# OpenPack_BATMOD_V2p0_USBA.net
KiCad netlist of a schematic drawn in Altium Designer
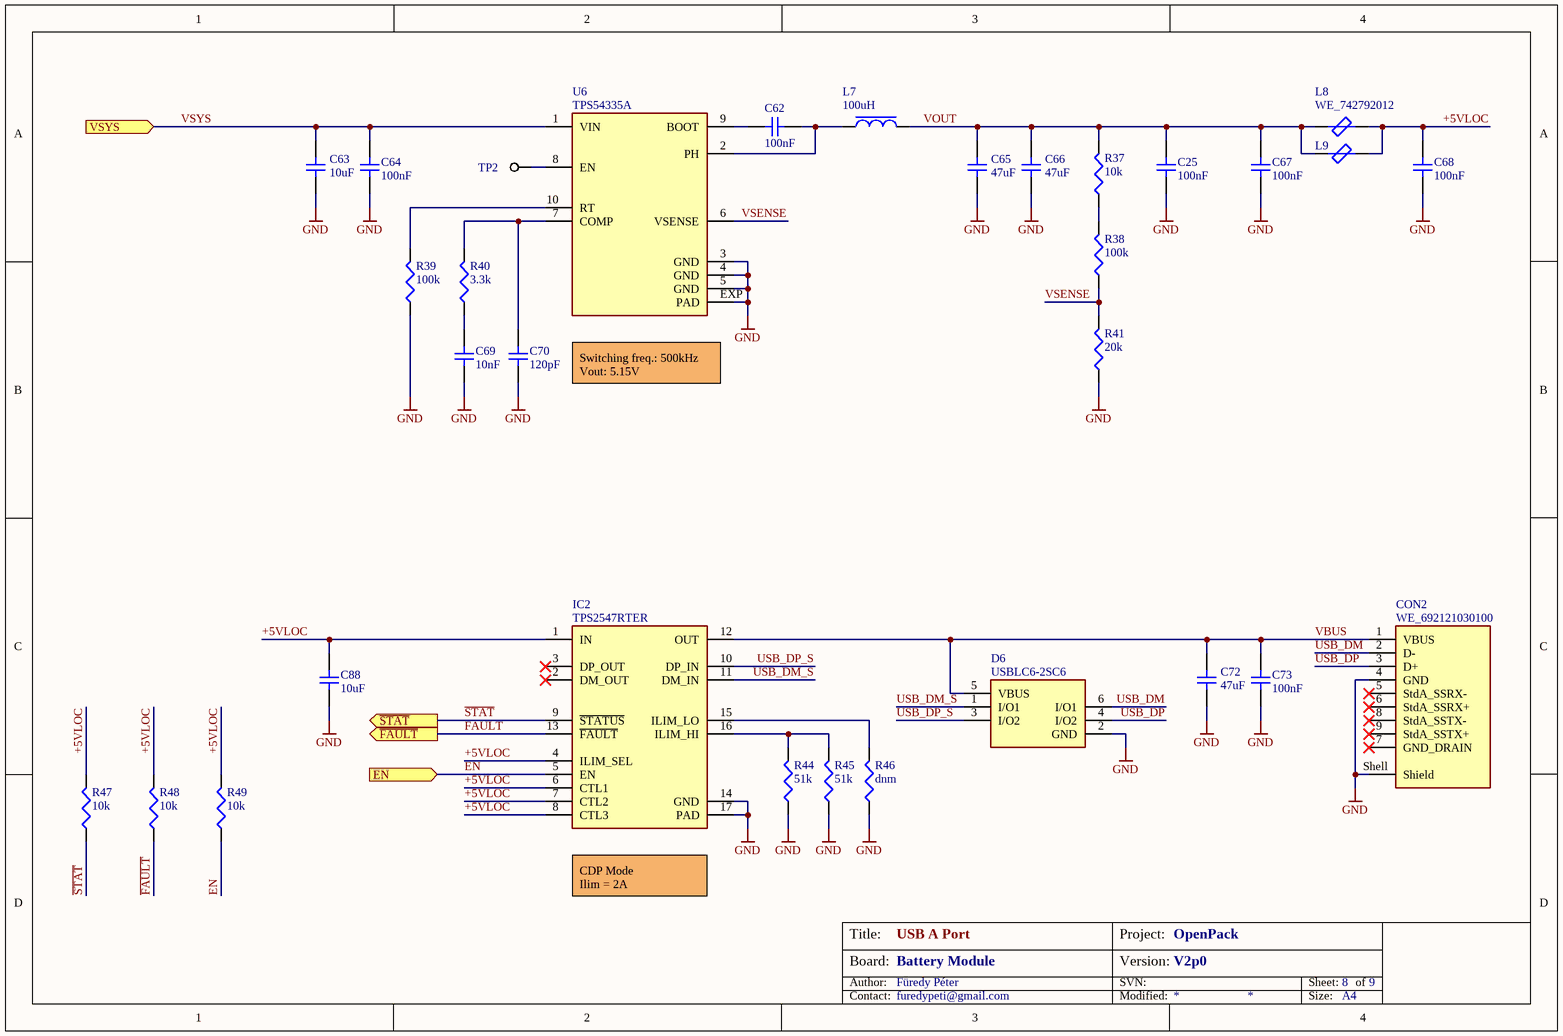
[diagram p0: OpenPack_BATMOD_V2p0_USBA.SchDoc]

(export (version "E")
  (design (tool "Eeschema 10.0.6"))
  (components
    (comp (ref "C25")
      (value "100nF")
      (footprint "CAP_0603")
      (description "MLCC capacitor")
      (libsource (lib "SCHLIB") (part "NP-CAPACITOR"))
    )
    (comp (ref "C62")
      (value "100nF")
      (footprint "CAP_0603")
      (description "MLCC capacitor")
      (libsource (lib "SCHLIB") (part "NP-CAPACITOR"))
    )
    (comp (ref "C63")
      (value "10uF")
      (footprint "CAP_1210")
      (description "UMK325BJ106KM-P")
      (fields (field (name "PART NUMBER") "810-CGA6P1X7R1N106K2"))
      (libsource (lib "SCHLIB") (part "NP-CAPACITOR"))
    )
    (comp (ref "C64")
      (value "100nF")
      (footprint "CAP_0603")
      (description "MLCC capacitor")
      (libsource (lib "SCHLIB") (part "NP-CAPACITOR"))
    )
    (comp (ref "C65")
      (value "47uF")
      (footprint "CAP_1210")
      (description "Np-Cap")
      (fields (field (name "PART NUMBER") "80-C1210C476M4P"))
      (libsource (lib "SCHLIB") (part "NP-CAPACITOR"))
    )
    (comp (ref "C66")
      (value "47uF")
      (footprint "CAP_1210")
      (description "Np-Cap")
      (fields (field (name "PART NUMBER") "80-C1210C476M4P"))
      (libsource (lib "SCHLIB") (part "NP-CAPACITOR"))
    )
    (comp (ref "C67")
      (value "100nF")
      (footprint "CAP_0603")
      (description "MLCC capacitor")
      (libsource (lib "SCHLIB") (part "NP-CAPACITOR"))
    )
    (comp (ref "C68")
      (value "100nF")
      (footprint "CAP_0603")
      (description "MLCC capacitor")
      (libsource (lib "SCHLIB") (part "NP-CAPACITOR"))
    )
    (comp (ref "C69")
      (value "10nF")
      (footprint "CAP_0603")
      (description "MLCC capacitor")
      (libsource (lib "SCHLIB") (part "NP-CAPACITOR"))
    )
    (comp (ref "C70")
      (value "120pF")
      (footprint "CAP_0603")
      (description "MLCC capacitor")
      (libsource (lib "SCHLIB") (part "NP-CAPACITOR"))
    )
    (comp (ref "C72")
      (value "47uF")
      (footprint "CAP_1210")
      (description "Np-Cap")
      (fields (field (name "PART NUMBER") "80-C1210C476M4P"))
      (libsource (lib "SCHLIB") (part "NP-CAPACITOR"))
    )
    (comp (ref "C73")
      (value "100nF")
      (footprint "CAP_0603")
      (description "MLCC capacitor")
      (libsource (lib "SCHLIB") (part "NP-CAPACITOR"))
    )
    (comp (ref "C88")
      (value "10uF")
      (footprint "CAP_0603")
      (description "MLCC capacitor")
      (libsource (lib "SCHLIB") (part "NP-CAPACITOR"))
    )
    (comp (ref "CON2")
      (value "WE_692121030100")
      (footprint "WE_692121030100")
      (description "USB Connectors WR-COM 3.0 TypeA SMT 9Pin Horztl Female")
      (fields (field (name "PART NUMBER") "710-692121030100"))
      (libsource (lib "SCHLIB") (part "WE_692121030100"))
    )
    (comp (ref "D6")
      (value "USBLC6-2SC6")
      (footprint "SOT-23-6")
      (description "ESD Protection Diodes / TVS Diodes ESD Protection Low Cap")
      (fields (field (name "PART NUMBER") "511-USBLC6-2SC6"))
      (libsource (lib "SCHLIB") (part "USBLC6-2SC6"))
    )
    (comp (ref "IC2")
      (value "TPS2547RTER")
      (footprint "QFN-16")
      (description "USB Switch ICs USB charging port co ntroller and 3A pow A 595-TPS2547RTET")
      (fields (field (name "PART NUMBER") "595-TPS2547RTER"))
      (libsource (lib "SCHLIB") (part "TPS2547RTER"))
    )
    (comp (ref "L7")
      (value "100uH")
      (footprint "IND_2")
      (description "Ferrit core coil, 22uH 2.85A, 75mR")
      (fields (field (name "PART NUMBER") "994-MSS1038T-223MLC"))
      (libsource (lib "SCHLIB") (part "Inductance - 22uH"))
    )
    (comp (ref "L8")
      (value "WE_742792012")
      (footprint "IND-0805")
      (description "Chip Ferrite Bead, 33R @100MHz, 4A")
      (fields (field (name "PART NUMBER") "710-742792012"))
      (libsource (lib "SCHLIB") (part "WE_742792012"))
    )
    (comp (ref "L9")
      (value "WE_742792012")
      (footprint "IND-0805")
      (description "Chip Ferrite Bead, 33R @100MHz, 4A")
      (fields (field (name "PART NUMBER") "710-742792012"))
      (libsource (lib "SCHLIB") (part "WE_742792012"))
    )
    (comp (ref "R37")
      (value "10k")
      (footprint "RES-0603")
      (description "Metal Film Resistor")
      (libsource (lib "SCHLIB") (part "RESISTOR"))
    )
    (comp (ref "R38")
      (value "100k")
      (footprint "RES-0603")
      (description "Metal Film Resistor")
      (libsource (lib "SCHLIB") (part "RESISTOR"))
    )
    (comp (ref "R39")
      (value "100k")
      (footprint "RES-0603")
      (description "Metal Film Resistor")
      (libsource (lib "SCHLIB") (part "RESISTOR"))
    )
    (comp (ref "R40")
      (value "3.3k")
      (footprint "RES-0603")
      (description "Metal Film Resistor")
      (libsource (lib "SCHLIB") (part "RESISTOR"))
    )
    (comp (ref "R41")
      (value "20k")
      (footprint "RES-0603")
      (description "Metal Film Resistor")
      (libsource (lib "SCHLIB") (part "RESISTOR"))
    )
    (comp (ref "R44")
      (value "51k")
      (footprint "RES-0603")
      (description "Metal Film Resistor")
      (libsource (lib "SCHLIB") (part "RESISTOR"))
    )
    (comp (ref "R45")
      (value "51k")
      (footprint "RES-0603")
      (description "Metal Film Resistor")
      (libsource (lib "SCHLIB") (part "RESISTOR"))
    )
    (comp (ref "R46")
      (value "dnm")
      (footprint "RES-0603")
      (description "Metal Film Resistor")
      (libsource (lib "SCHLIB") (part "RESISTOR"))
    )
    (comp (ref "R47")
      (value "10k")
      (footprint "RES-0603")
      (description "Metal Film Resistor")
      (libsource (lib "SCHLIB") (part "RESISTOR"))
    )
    (comp (ref "R48")
      (value "10k")
      (footprint "RES-0603")
      (description "Metal Film Resistor")
      (libsource (lib "SCHLIB") (part "RESISTOR"))
    )
    (comp (ref "R49")
      (value "10k")
      (footprint "RES-0603")
      (description "Metal Film Resistor")
      (libsource (lib "SCHLIB") (part "RESISTOR"))
    )
    (comp (ref "TP2")
      (value "TESTPOINT")
      (footprint "TESTPOINT1MM")
      (description "SMD testpoint")
      (libsource (lib "SCHLIB") (part "TESTPOINT"))
    )
    (comp (ref "U6")
      (value "TPS54335A")
      (footprint "VSON-10")
      (description "Switching Voltage Regulators 4.5Vto28VInp 3A Sync Step-Down Converter A 595-TPS54335ADRCT")
      (fields (field (name "PART NUMBER") "595-TPS54335ADRCR"))
      (libsource (lib "SCHLIB") (part "TPS54335A"))
    )
  )
  (nets
    (net (code "1") (name "/+5VLOC") (class "Default")
      (node (ref "C68") (pin "1") (pinfunction "1_1") (pintype "passive"))
      (node (ref "C88") (pin "2") (pinfunction "2_2") (pintype "passive"))
      (node (ref "IC2") (pin "1") (pinfunction "IN_1") (pintype "passive"))
      (node (ref "IC2") (pin "4") (pinfunction "ILIM_SEL_4") (pintype "passive"))
      (node (ref "IC2") (pin "6") (pinfunction "CTL1_6") (pintype "passive"))
      (node (ref "IC2") (pin "7") (pinfunction "CTL2_7") (pintype "passive"))
      (node (ref "IC2") (pin "8") (pinfunction "CTL3_8") (pintype "passive"))
      (node (ref "L8") (pin "2") (pinfunction "2_2") (pintype "passive"))
      (node (ref "L9") (pin "2") (pinfunction "2_2") (pintype "passive"))
      (node (ref "R47") (pin "2") (pintype "passive"))
      (node (ref "R48") (pin "2") (pintype "passive"))
      (node (ref "R49") (pin "2") (pintype "passive"))
    )
    (net (code "2") (name "/EN") (class "Default")
      (node (ref "IC2") (pin "5") (pinfunction "EN_5") (pintype "passive"))
      (node (ref "R49") (pin "1") (pintype "passive"))
    )
    (net (code "3") (name "/USB_DM") (class "Default")
      (node (ref "CON2") (pin "2") (pinfunction "D-_2") (pintype "passive"))
      (node (ref "D6") (pin "6") (pinfunction "I/O1_6") (pintype "passive"))
    )
    (net (code "4") (name "/USB_DM_S") (class "Default")
      (node (ref "D6") (pin "1") (pinfunction "I/O1_1") (pintype "passive"))
      (node (ref "IC2") (pin "11") (pinfunction "DM_IN_11") (pintype "passive"))
    )
    (net (code "5") (name "/USB_DP") (class "Default")
      (node (ref "CON2") (pin "3") (pinfunction "D+_3") (pintype "passive"))
      (node (ref "D6") (pin "4") (pinfunction "I/O2_4") (pintype "passive"))
    )
    (net (code "6") (name "/USB_DP_S") (class "Default")
      (node (ref "D6") (pin "3") (pinfunction "I/O2_3") (pintype "passive"))
      (node (ref "IC2") (pin "10") (pinfunction "DP_IN_10") (pintype "passive"))
    )
    (net (code "7") (name "/VBUS") (class "Default")
      (node (ref "C72") (pin "2") (pinfunction "2_2") (pintype "passive"))
      (node (ref "C73") (pin "1") (pinfunction "1_1") (pintype "passive"))
      (node (ref "CON2") (pin "1") (pinfunction "VBUS_1") (pintype "passive"))
      (node (ref "D6") (pin "5") (pinfunction "VBUS_5") (pintype "passive"))
      (node (ref "IC2") (pin "12") (pinfunction "OUT_12") (pintype "passive"))
    )
    (net (code "8") (name "/VOUT") (class "Default")
      (node (ref "C25") (pin "1") (pinfunction "1_1") (pintype "passive"))
      (node (ref "C65") (pin "2") (pinfunction "2_2") (pintype "passive"))
      (node (ref "C66") (pin "2") (pinfunction "2_2") (pintype "passive"))
      (node (ref "C67") (pin "1") (pinfunction "1_1") (pintype "passive"))
      (node (ref "L7") (pin "2") (pinfunction "2_2") (pintype "passive"))
      (node (ref "L8") (pin "1") (pinfunction "1_1") (pintype "passive"))
      (node (ref "L9") (pin "1") (pinfunction "1_1") (pintype "passive"))
      (node (ref "R37") (pin "2") (pintype "passive"))
    )
    (net (code "9") (name "/VSENSE") (class "Default")
      (node (ref "R38") (pin "1") (pintype "passive"))
      (node (ref "R41") (pin "2") (pintype "passive"))
      (node (ref "U6") (pin "6") (pinfunction "VSENSE_6") (pintype "passive"))
    )
    (net (code "10") (name "/VSYS") (class "Default")
      (node (ref "C63") (pin "2") (pinfunction "2_2") (pintype "passive"))
      (node (ref "C64") (pin "1") (pinfunction "1_1") (pintype "passive"))
      (node (ref "U6") (pin "1") (pinfunction "VIN_1") (pintype "passive"))
    )
    (net (code "11") (name "/~{FAULT}") (class "Default")
      (node (ref "IC2") (pin "13") (pinfunction "~{FAULT}_13") (pintype "passive"))
      (node (ref "R48") (pin "1") (pintype "passive"))
    )
    (net (code "12") (name "/~{STAT}") (class "Default")
      (node (ref "IC2") (pin "9") (pinfunction "~{STATUS}_9") (pintype "passive"))
      (node (ref "R47") (pin "1") (pintype "passive"))
    )
    (net (code "13") (name "GND") (class "Default")
      (node (ref "C25") (pin "2") (pinfunction "2_2") (pintype "passive"))
      (node (ref "C63") (pin "1") (pinfunction "1_1") (pintype "passive"))
      (node (ref "C64") (pin "2") (pinfunction "2_2") (pintype "passive"))
      (node (ref "C65") (pin "1") (pinfunction "1_1") (pintype "passive"))
      (node (ref "C66") (pin "1") (pinfunction "1_1") (pintype "passive"))
      (node (ref "C67") (pin "2") (pinfunction "2_2") (pintype "passive"))
      (node (ref "C68") (pin "2") (pinfunction "2_2") (pintype "passive"))
      (node (ref "C69") (pin "2") (pinfunction "2_2") (pintype "passive"))
      (node (ref "C70") (pin "2") (pinfunction "2_2") (pintype "passive"))
      (node (ref "C72") (pin "1") (pinfunction "1_1") (pintype "passive"))
      (node (ref "C73") (pin "2") (pinfunction "2_2") (pintype "passive"))
      (node (ref "C88") (pin "1") (pinfunction "1_1") (pintype "passive"))
      (node (ref "CON2") (pin "4") (pinfunction "GND_4") (pintype "passive"))
      (node (ref "CON2") (pin "Shell") (pinfunction "Shield_Shell") (pintype "passive"))
      (node (ref "D6") (pin "2") (pinfunction "GND_2") (pintype "passive"))
      (node (ref "IC2") (pin "14") (pinfunction "GND_14") (pintype "passive"))
      (node (ref "IC2") (pin "17") (pinfunction "PAD_17") (pintype "passive"))
      (node (ref "R39") (pin "1") (pintype "passive"))
      (node (ref "R41") (pin "1") (pintype "passive"))
      (node (ref "R44") (pin "1") (pintype "passive"))
      (node (ref "R45") (pin "1") (pintype "passive"))
      (node (ref "R46") (pin "1") (pintype "passive"))
      (node (ref "U6") (pin "3") (pinfunction "GND_3") (pintype "passive"))
      (node (ref "U6") (pin "4") (pinfunction "GND_4") (pintype "passive"))
      (node (ref "U6") (pin "5") (pinfunction "GND_5") (pintype "passive"))
      (node (ref "U6") (pin "EXP") (pinfunction "PAD_EXP") (pintype "passive"))
    )
    (net (code "14") (name "Net-(C69-Pad1)") (class "Default")
      (node (ref "C69") (pin "1") (pinfunction "1_1") (pintype "passive"))
      (node (ref "R40") (pin "1") (pintype "passive"))
    )
    (net (code "15") (name "Net-(IC2-ILIM_HI)") (class "Default")
      (node (ref "IC2") (pin "16") (pinfunction "ILIM_HI_16") (pintype "passive"))
      (node (ref "R44") (pin "2") (pintype "passive"))
      (node (ref "R45") (pin "2") (pintype "passive"))
    )
    (net (code "16") (name "Net-(IC2-ILIM_LO)") (class "Default")
      (node (ref "IC2") (pin "15") (pinfunction "ILIM_LO_15") (pintype "passive"))
      (node (ref "R46") (pin "2") (pintype "passive"))
    )
    (net (code "17") (name "Net-(R37-Pad1)") (class "Default")
      (node (ref "R37") (pin "1") (pintype "passive"))
      (node (ref "R38") (pin "2") (pintype "passive"))
    )
    (net (code "18") (name "Net-(U6-BOOT)") (class "Default")
      (node (ref "C62") (pin "2") (pinfunction "2_2") (pintype "passive"))
      (node (ref "U6") (pin "9") (pinfunction "BOOT_9") (pintype "passive"))
    )
    (net (code "19") (name "Net-(U6-COMP)") (class "Default")
      (node (ref "C70") (pin "1") (pinfunction "1_1") (pintype "passive"))
      (node (ref "R40") (pin "2") (pintype "passive"))
      (node (ref "U6") (pin "7") (pinfunction "COMP_7") (pintype "passive"))
    )
    (net (code "20") (name "Net-(U6-EN)") (class "Default")
      (node (ref "TP2") (pin "0") (pintype "passive"))
      (node (ref "U6") (pin "8") (pinfunction "EN_8") (pintype "passive"))
    )
    (net (code "21") (name "Net-(U6-PH)") (class "Default")
      (node (ref "C62") (pin "1") (pinfunction "1_1") (pintype "passive"))
      (node (ref "L7") (pin "1") (pinfunction "1_1") (pintype "passive"))
      (node (ref "U6") (pin "2") (pinfunction "PH_2") (pintype "passive"))
    )
    (net (code "22") (name "Net-(U6-RT)") (class "Default")
      (node (ref "R39") (pin "2") (pintype "passive"))
      (node (ref "U6") (pin "10") (pinfunction "RT_10") (pintype "passive"))
    )
    (net (code "23") (name "unconnected-(CON2-GND_DRAIN-Pad7)") (class "Default")
      (node (ref "CON2") (pin "7") (pinfunction "GND_DRAIN_7") (pintype "passive+no_connect"))
    )
    (net (code "24") (name "unconnected-(CON2-StdA_SSRX+-Pad6)") (class "Default")
      (node (ref "CON2") (pin "6") (pinfunction "StdA_SSRX+_6") (pintype "passive+no_connect"))
    )
    (net (code "25") (name "unconnected-(CON2-StdA_SSRX--Pad5)") (class "Default")
      (node (ref "CON2") (pin "5") (pinfunction "StdA_SSRX-_5") (pintype "passive+no_connect"))
    )
    (net (code "26") (name "unconnected-(CON2-StdA_SSTX+-Pad9)") (class "Default")
      (node (ref "CON2") (pin "9") (pinfunction "StdA_SSTX+_9") (pintype "passive+no_connect"))
    )
    (net (code "27") (name "unconnected-(CON2-StdA_SSTX--Pad8)") (class "Default")
      (node (ref "CON2") (pin "8") (pinfunction "StdA_SSTX-_8") (pintype "passive+no_connect"))
    )
    (net (code "28") (name "unconnected-(IC2-DM_OUT-Pad2)") (class "Default")
      (node (ref "IC2") (pin "2") (pinfunction "DM_OUT_2") (pintype "passive+no_connect"))
    )
    (net (code "29") (name "unconnected-(IC2-DP_OUT-Pad3)") (class "Default")
      (node (ref "IC2") (pin "3") (pinfunction "DP_OUT_3") (pintype "passive+no_connect"))
    )
  )
)
